# Controller.net
KiCad netlist of a schematic drawn in EAGLE
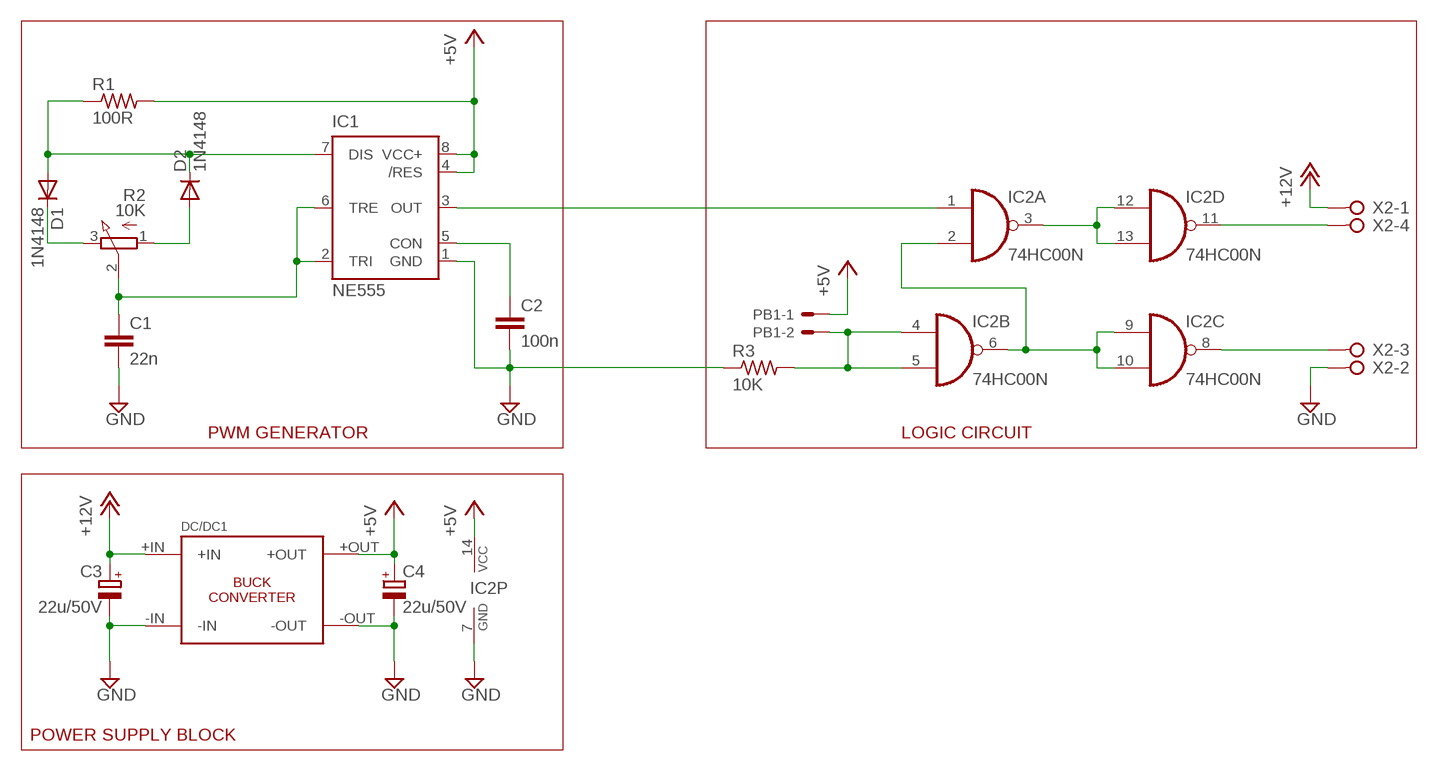
[diagram p0: schematic, sheet 1]

(export (version "E")
  (design (tool "Eeschema 10.0.6"))
  (components
    (comp (ref "C1")
      (value "22n")
      (footprint "eagle-import:C050-035X075")
      (libsource (lib "eagle-import") (part "C-EU050-035X075"))
    )
    (comp (ref "C2")
      (value "100n")
      (footprint "eagle-import:C075-032X103")
      (libsource (lib "eagle-import") (part "rcl_334_C-EU075-032X103"))
    )
    (comp (ref "C3")
      (value "22u/50V")
      (footprint "eagle-import:E2,5-6")
      (libsource (lib "eagle-import") (part "CPOL-EUE2.5-6"))
    )
    (comp (ref "C4")
      (value "22u/50V")
      (footprint "eagle-import:E2,5-6")
      (libsource (lib "eagle-import") (part "CPOL-EUE2.5-6"))
    )
    (comp (ref "D1")
      (value "1N4148")
      (footprint "eagle-import:DO35-10")
      (libsource (lib "eagle-import") (part "1N4148"))
    )
    (comp (ref "D2")
      (value "1N4148")
      (footprint "eagle-import:DO35-10")
      (libsource (lib "eagle-import") (part "1N4148"))
    )
    (comp (ref "DC/DC1")
      (value "MP1548EN")
      (footprint "eagle-import:MP1548EN")
      (libsource (lib "eagle-import") (part "MP1548EN"))
    )
    (comp (ref "IC1")
      (value "NE555")
      (footprint "eagle-import:DIL-08")
      (fields (field (name "MF") "Arrow Electronics") (field (name "MPN") "NE555N"))
      (libsource (lib "eagle-import") (part "NE555"))
    )
    (comp (ref "IC2")
      (value "74HC00N")
      (footprint "eagle-import:DIL14")
      (libsource (lib "eagle-import") (part "7400NHC"))
    )
    (comp (ref "PB1")
      (value "22-23-2021")
      (footprint "eagle-import:22-23-2021")
      (fields (field (name "MF") "MOLEX"))
      (libsource (lib "eagle-import") (part "22-23-2021"))
    )
    (comp (ref "R1")
      (value "100R")
      (footprint "eagle-import:0207_12")
      (libsource (lib "eagle-import") (part "R-US_0207/12"))
    )
    (comp (ref "R2")
      (value "10K")
      (footprint "eagle-import:3RP_1610N")
      (libsource (lib "eagle-import") (part "3RP/1610N"))
    )
    (comp (ref "R3")
      (value "10K")
      (footprint "eagle-import:0207_12")
      (libsource (lib "eagle-import") (part "R-US_0207/12"))
    )
    (comp (ref "X2")
      (value "W237-04P")
      (footprint "eagle-import:W237-4P")
      (libsource (lib "eagle-import") (part "W237-04P"))
    )
  )
  (nets
    (net (code "1") (name "+5V") (class "Default")
      (node (ref "C4") (pin "+") (pinfunction "+_+") (pintype "passive"))
      (node (ref "DC/DC1") (pin "+OUT") (pinfunction "+OUT_+OUT") (pintype "bidirectional"))
      (node (ref "IC1") (pin "4") (pinfunction "/RES_4") (pintype "input"))
      (node (ref "IC1") (pin "8") (pinfunction "VCC+_8") (pintype "power_in"))
      (node (ref "IC2") (pin "14") (pinfunction "VCC_14") (pintype "power_in"))
      (node (ref "PB1") (pin "1") (pinfunction "S_1") (pintype "passive"))
      (node (ref "R1") (pin "2") (pinfunction "2_2") (pintype "passive"))
    )
    (net (code "2") (name "+12V") (class "Default")
      (node (ref "C3") (pin "+") (pinfunction "+_+") (pintype "passive"))
      (node (ref "DC/DC1") (pin "+IN") (pinfunction "+IN_+IN") (pintype "bidirectional"))
      (node (ref "X2") (pin "1") (pinfunction "KL_1") (pintype "passive"))
    )
    (net (code "3") (name "GND") (class "Default")
      (node (ref "C1") (pin "2") (pinfunction "2_2") (pintype "passive"))
      (node (ref "C2") (pin "2") (pinfunction "2_2") (pintype "passive"))
      (node (ref "C3") (pin "-") (pinfunction "-_-") (pintype "passive"))
      (node (ref "C4") (pin "-") (pinfunction "-_-") (pintype "passive"))
      (node (ref "DC/DC1") (pin "-IN") (pinfunction "-IN_-IN") (pintype "bidirectional"))
      (node (ref "DC/DC1") (pin "-OUT") (pinfunction "-OUT_-OUT") (pintype "bidirectional"))
      (node (ref "IC1") (pin "1") (pinfunction "GND_1") (pintype "power_in"))
      (node (ref "IC2") (pin "7") (pinfunction "GND_7") (pintype "power_in"))
      (node (ref "R3") (pin "1") (pinfunction "1_1") (pintype "passive"))
      (node (ref "X2") (pin "2") (pinfunction "KL_2") (pintype "passive"))
    )
    (net (code "4") (name "Net-(IC1-CON)") (class "Default")
      (node (ref "C2") (pin "1") (pinfunction "1_1") (pintype "passive"))
      (node (ref "IC1") (pin "5") (pinfunction "CON_5") (pintype "input"))
    )
    (net (code "5") (name "Net-(IC1-DIS)") (class "Default")
      (node (ref "D1") (pin "A") (pinfunction "A_A") (pintype "passive"))
      (node (ref "D2") (pin "C") (pinfunction "C_C") (pintype "passive"))
      (node (ref "IC1") (pin "7") (pinfunction "DIS_7") (pintype "input"))
      (node (ref "R1") (pin "1") (pinfunction "1_1") (pintype "passive"))
    )
    (net (code "6") (name "Net-(IC1-OUT)") (class "Default")
      (node (ref "IC1") (pin "3") (pinfunction "OUT_3") (pintype "output"))
      (node (ref "IC2") (pin "1") (pinfunction "I0_1") (pintype "input"))
    )
    (net (code "7") (name "Net-(IC1-TRE)") (class "Default")
      (node (ref "C1") (pin "1") (pinfunction "1_1") (pintype "passive"))
      (node (ref "IC1") (pin "2") (pinfunction "TRI_2") (pintype "input"))
      (node (ref "IC1") (pin "6") (pinfunction "TRE_6") (pintype "input"))
      (node (ref "R2") (pin "2") (pinfunction "S_2") (pintype "passive"))
    )
    (net (code "8") (name "Net-(IC2A-I1)") (class "Default")
      (node (ref "IC2") (pin "10") (pinfunction "I1_10") (pintype "input"))
      (node (ref "IC2") (pin "2") (pinfunction "I1_2") (pintype "input"))
      (node (ref "IC2") (pin "6") (pinfunction "O_6") (pintype "output"))
      (node (ref "IC2") (pin "9") (pinfunction "I0_9") (pintype "input"))
    )
    (net (code "9") (name "Net-(IC2A-O)") (class "Default")
      (node (ref "IC2") (pin "12") (pinfunction "I0_12") (pintype "input"))
      (node (ref "IC2") (pin "13") (pinfunction "I1_13") (pintype "input"))
      (node (ref "IC2") (pin "3") (pinfunction "O_3") (pintype "output"))
    )
    (net (code "10") (name "Net-(IC2B-I0)") (class "Default")
      (node (ref "IC2") (pin "4") (pinfunction "I0_4") (pintype "input"))
      (node (ref "IC2") (pin "5") (pinfunction "I1_5") (pintype "input"))
      (node (ref "PB1") (pin "2") (pinfunction "S_2") (pintype "passive"))
      (node (ref "R3") (pin "2") (pinfunction "2_2") (pintype "passive"))
    )
    (net (code "11") (name "Net-(IC2C-O)") (class "Default")
      (node (ref "IC2") (pin "8") (pinfunction "O_8") (pintype "output"))
      (node (ref "X2") (pin "3") (pinfunction "KL_3") (pintype "passive"))
    )
    (net (code "12") (name "Net-(IC2D-O)") (class "Default")
      (node (ref "IC2") (pin "11") (pinfunction "O_11") (pintype "output"))
      (node (ref "X2") (pin "4") (pinfunction "KL_4") (pintype "passive"))
    )
    (net (code "13") (name "Net-(R2-A)") (class "Default")
      (node (ref "D2") (pin "A") (pinfunction "A_A") (pintype "passive"))
      (node (ref "R2") (pin "1") (pinfunction "A_1") (pintype "passive"))
    )
    (net (code "14") (name "Net-(R2-E)") (class "Default")
      (node (ref "D1") (pin "C") (pinfunction "C_C") (pintype "passive"))
      (node (ref "R2") (pin "3") (pinfunction "E_3") (pintype "passive"))
    )
  )
)
